# 7_Motor_Control.net
KiCad netlist of a schematic drawn in Altium Designer
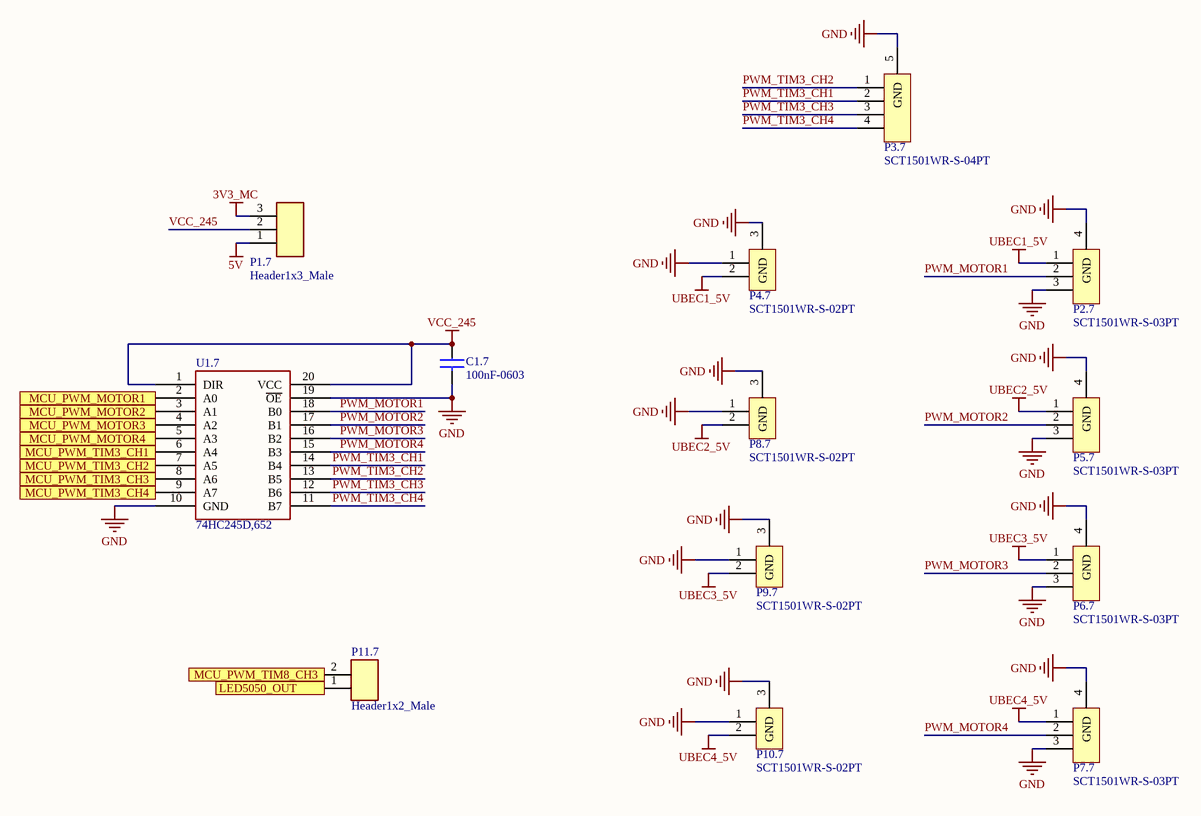
[diagram p0: [7] Motor_Control.SchDoc]

(export (version "E")
  (design (tool "Eeschema 10.0.6"))
  (components
    (comp (ref "C1.7")
      (value "100nF-0603")
      (footprint "CAP0603")
      (description "CAP CER 0.1UF 50V X7R 0603")
      (fields (field (name "TOLERANCE") "±10%"))
      (libsource (lib "Minh_Lib") (part "CC0603KRX7R9BB104"))
    )
    (comp (ref "P1.7")
      (value "Header1x3_Male")
      (footprint "Minh_Lib:HDR1x3_2.54_MALE")
      (description "Header1x3_2.54_MALE")
      (libsource (lib "Minh_Lib") (part "HDR1x3_2.54_MALE"))
    )
    (comp (ref "P2.7")
      (value "SCT1501WR-S-03PT")
      (footprint "Connector ZH1.5 3P SMD")
      (libsource (lib "Minh_Lib") (part "SCT1501WR-S-03PT"))
    )
    (comp (ref "P3.7")
      (value "SCT1501WR-S-04PT")
      (footprint "Connector ZH1.5 4P SMD")
      (libsource (lib "Minh_Lib") (part "SCT1501WR-S-04PT"))
    )
    (comp (ref "P4.7")
      (value "SCT1501WR-S-02PT")
      (footprint "Connector ZH1.5 2P SMD")
      (libsource (lib "Minh_Lib") (part "SCT1501WR-S-02PT"))
    )
    (comp (ref "P5.7")
      (value "SCT1501WR-S-03PT")
      (footprint "Connector ZH1.5 3P SMD")
      (libsource (lib "Minh_Lib") (part "SCT1501WR-S-03PT"))
    )
    (comp (ref "P6.7")
      (value "SCT1501WR-S-03PT")
      (footprint "Connector ZH1.5 3P SMD")
      (libsource (lib "Minh_Lib") (part "SCT1501WR-S-03PT"))
    )
    (comp (ref "P7.7")
      (value "SCT1501WR-S-03PT")
      (footprint "Connector ZH1.5 3P SMD")
      (libsource (lib "Minh_Lib") (part "SCT1501WR-S-03PT"))
    )
    (comp (ref "P8.7")
      (value "SCT1501WR-S-02PT")
      (footprint "Connector ZH1.5 2P SMD")
      (libsource (lib "Minh_Lib") (part "SCT1501WR-S-02PT"))
    )
    (comp (ref "P9.7")
      (value "SCT1501WR-S-02PT")
      (footprint "Connector ZH1.5 2P SMD")
      (libsource (lib "Minh_Lib") (part "SCT1501WR-S-02PT"))
    )
    (comp (ref "P10.7")
      (value "SCT1501WR-S-02PT")
      (footprint "Connector ZH1.5 2P SMD")
      (libsource (lib "Minh_Lib") (part "SCT1501WR-S-02PT"))
    )
    (comp (ref "P11.7")
      (value "Header1x2_Male")
      (footprint "Minh_Lib:HDR1x2_2.54_MALE")
      (description "Header1x2_2.54_MALE")
      (libsource (lib "Minh_Lib") (part "HDR1x2_2.54_MALE"))
    )
    (comp (ref "U1.7")
      (value "74HC245D,652")
      (footprint "SOT163-1_NEX")
      (fields (field (name "COPYRIGHT") "Copyright (C) 2016 Accelerated Designs. All rights reserved"))
      (libsource (lib "Minh_Lib") (part "74HC245D,652"))
    )
  )
  (nets
    (net (code "1") (name "/LED5050_OUT") (class "Default")
      (node (ref "P11.7") (pin "1") (pinfunction "1_1") (pintype "passive"))
    )
    (net (code "2") (name "/MCU_PWM_MOTOR1") (class "Default")
      (node (ref "U1.7") (pin "2") (pinfunction "A0_2") (pintype "passive"))
    )
    (net (code "3") (name "/MCU_PWM_MOTOR2") (class "Default")
      (node (ref "U1.7") (pin "3") (pinfunction "A1_3") (pintype "passive"))
    )
    (net (code "4") (name "/MCU_PWM_MOTOR3") (class "Default")
      (node (ref "U1.7") (pin "4") (pinfunction "A2_4") (pintype "passive"))
    )
    (net (code "5") (name "/MCU_PWM_MOTOR4") (class "Default")
      (node (ref "U1.7") (pin "5") (pinfunction "A3_5") (pintype "passive"))
    )
    (net (code "6") (name "/MCU_PWM_TIM3_CH1") (class "Default")
      (node (ref "U1.7") (pin "6") (pinfunction "A4_6") (pintype "passive"))
    )
    (net (code "7") (name "/MCU_PWM_TIM3_CH2") (class "Default")
      (node (ref "U1.7") (pin "7") (pinfunction "A5_7") (pintype "passive"))
    )
    (net (code "8") (name "/MCU_PWM_TIM3_CH3") (class "Default")
      (node (ref "U1.7") (pin "8") (pinfunction "A6_8") (pintype "passive"))
    )
    (net (code "9") (name "/MCU_PWM_TIM3_CH4") (class "Default")
      (node (ref "U1.7") (pin "9") (pinfunction "A7_9") (pintype "passive"))
    )
    (net (code "10") (name "/MCU_PWM_TIM8_CH3") (class "Default")
      (node (ref "P11.7") (pin "2") (pinfunction "2_2") (pintype "passive"))
    )
    (net (code "11") (name "/PWM_MOTOR1") (class "Default")
      (node (ref "P2.7") (pin "2") (pinfunction "2_2") (pintype "passive"))
      (node (ref "U1.7") (pin "18") (pinfunction "B0_18") (pintype "passive"))
    )
    (net (code "12") (name "/PWM_MOTOR2") (class "Default")
      (node (ref "P5.7") (pin "2") (pinfunction "2_2") (pintype "passive"))
      (node (ref "U1.7") (pin "17") (pinfunction "B1_17") (pintype "passive"))
    )
    (net (code "13") (name "/PWM_MOTOR3") (class "Default")
      (node (ref "P6.7") (pin "2") (pinfunction "2_2") (pintype "passive"))
      (node (ref "U1.7") (pin "16") (pinfunction "B2_16") (pintype "passive"))
    )
    (net (code "14") (name "/PWM_MOTOR4") (class "Default")
      (node (ref "P7.7") (pin "2") (pinfunction "2_2") (pintype "passive"))
      (node (ref "U1.7") (pin "15") (pinfunction "B3_15") (pintype "passive"))
    )
    (net (code "15") (name "/PWM_TIM3_CH1") (class "Default")
      (node (ref "P3.7") (pin "2") (pinfunction "2_2") (pintype "passive"))
      (node (ref "U1.7") (pin "14") (pinfunction "B4_14") (pintype "passive"))
    )
    (net (code "16") (name "/PWM_TIM3_CH2") (class "Default")
      (node (ref "P3.7") (pin "1") (pinfunction "1_1") (pintype "passive"))
      (node (ref "U1.7") (pin "13") (pinfunction "B5_13") (pintype "passive"))
    )
    (net (code "17") (name "/PWM_TIM3_CH3") (class "Default")
      (node (ref "P3.7") (pin "3") (pinfunction "3_3") (pintype "passive"))
      (node (ref "U1.7") (pin "12") (pinfunction "B6_12") (pintype "passive"))
    )
    (net (code "18") (name "/PWM_TIM3_CH4") (class "Default")
      (node (ref "P3.7") (pin "4") (pinfunction "4_4") (pintype "passive"))
      (node (ref "U1.7") (pin "11") (pinfunction "B7_11") (pintype "passive"))
    )
    (net (code "19") (name "3V3_MC") (class "Default")
      (node (ref "P1.7") (pin "3") (pinfunction "3_3") (pintype "passive"))
    )
    (net (code "20") (name "5V") (class "Default")
      (node (ref "P1.7") (pin "1") (pinfunction "1_1") (pintype "passive"))
    )
    (net (code "21") (name "GND") (class "Default")
      (node (ref "C1.7") (pin "2") (pinfunction "2_2") (pintype "passive"))
      (node (ref "P10.7") (pin "1") (pinfunction "1_1") (pintype "passive"))
      (node (ref "P10.7") (pin "3") (pinfunction "GND_3") (pintype "passive"))
      (node (ref "P2.7") (pin "3") (pinfunction "3_3") (pintype "passive"))
      (node (ref "P2.7") (pin "4") (pinfunction "GND_4") (pintype "passive"))
      (node (ref "P3.7") (pin "5") (pinfunction "GND_5") (pintype "passive"))
      (node (ref "P4.7") (pin "1") (pinfunction "1_1") (pintype "passive"))
      (node (ref "P4.7") (pin "3") (pinfunction "GND_3") (pintype "passive"))
      (node (ref "P5.7") (pin "3") (pinfunction "3_3") (pintype "passive"))
      (node (ref "P5.7") (pin "4") (pinfunction "GND_4") (pintype "passive"))
      (node (ref "P6.7") (pin "3") (pinfunction "3_3") (pintype "passive"))
      (node (ref "P6.7") (pin "4") (pinfunction "GND_4") (pintype "passive"))
      (node (ref "P7.7") (pin "3") (pinfunction "3_3") (pintype "passive"))
      (node (ref "P7.7") (pin "4") (pinfunction "GND_4") (pintype "passive"))
      (node (ref "P8.7") (pin "1") (pinfunction "1_1") (pintype "passive"))
      (node (ref "P8.7") (pin "3") (pinfunction "GND_3") (pintype "passive"))
      (node (ref "P9.7") (pin "1") (pinfunction "1_1") (pintype "passive"))
      (node (ref "P9.7") (pin "3") (pinfunction "GND_3") (pintype "passive"))
      (node (ref "U1.7") (pin "10") (pinfunction "GND_10") (pintype "passive"))
      (node (ref "U1.7") (pin "19") (pinfunction "~{OE}_19") (pintype "passive"))
    )
    (net (code "22") (name "UBEC1_5V") (class "Default")
      (node (ref "P2.7") (pin "1") (pinfunction "1_1") (pintype "passive"))
      (node (ref "P4.7") (pin "2") (pinfunction "2_2") (pintype "passive"))
    )
    (net (code "23") (name "UBEC2_5V") (class "Default")
      (node (ref "P5.7") (pin "1") (pinfunction "1_1") (pintype "passive"))
      (node (ref "P8.7") (pin "2") (pinfunction "2_2") (pintype "passive"))
    )
    (net (code "24") (name "UBEC3_5V") (class "Default")
      (node (ref "P6.7") (pin "1") (pinfunction "1_1") (pintype "passive"))
      (node (ref "P9.7") (pin "2") (pinfunction "2_2") (pintype "passive"))
    )
    (net (code "25") (name "UBEC4_5V") (class "Default")
      (node (ref "P10.7") (pin "2") (pinfunction "2_2") (pintype "passive"))
      (node (ref "P7.7") (pin "1") (pinfunction "1_1") (pintype "passive"))
    )
    (net (code "26") (name "VCC_245") (class "Default")
      (node (ref "C1.7") (pin "1") (pinfunction "1_1") (pintype "passive"))
      (node (ref "P1.7") (pin "2") (pinfunction "2_2") (pintype "passive"))
      (node (ref "U1.7") (pin "1") (pinfunction "DIR_1") (pintype "passive"))
      (node (ref "U1.7") (pin "20") (pinfunction "VCC_20") (pintype "passive"))
    )
  )
)
